# attiny_pwm.net
KiCad netlist of a schematic drawn in EAGLE
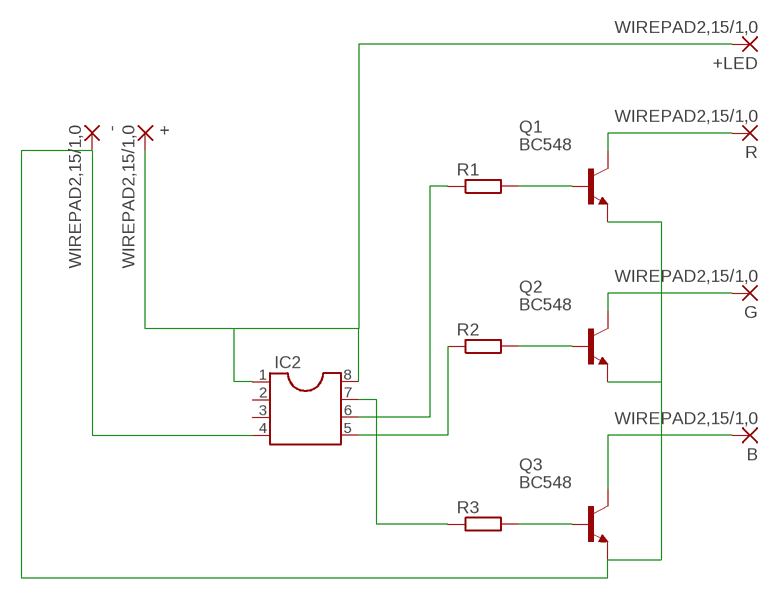
[diagram p0: schematic, sheet 1]

(export (version "E")
  (design (tool "Eeschema 10.0.6"))
  (components
    (comp (ref "+")
      (value "WIREPAD2,15/1,0")
      (footprint "eagle-import:2,15_1,0")
      (libsource (lib "eagle-import") (part "WIREPAD2,15/1,0"))
    )
    (comp (ref "+LED")
      (value "WIREPAD2,15/1,0")
      (footprint "eagle-import:2,15_1,0")
      (libsource (lib "eagle-import") (part "WIREPAD2,15/1,0"))
    )
    (comp (ref "-")
      (value "WIREPAD2,15/1,0")
      (footprint "eagle-import:2,15_1,0")
      (libsource (lib "eagle-import") (part "WIREPAD2,15/1,0"))
    )
    (comp (ref "B")
      (value "WIREPAD2,15/1,0")
      (footprint "eagle-import:2,15_1,0")
      (libsource (lib "eagle-import") (part "WIREPAD2,15/1,0"))
    )
    (comp (ref "G")
      (value "WIREPAD2,15/1,0")
      (footprint "eagle-import:2,15_1,0")
      (libsource (lib "eagle-import") (part "WIREPAD2,15/1,0"))
    )
    (comp (ref "IC2")
      (value "DIL8")
      (footprint "eagle-import:DIL08")
      (libsource (lib "eagle-import") (part "DIL8"))
    )
    (comp (ref "Q1")
      (value "BC548")
      (footprint "eagle-import:TO92-EBC")
      (libsource (lib "eagle-import") (part "BC548"))
    )
    (comp (ref "Q2")
      (value "BC548")
      (footprint "eagle-import:TO92-EBC")
      (libsource (lib "eagle-import") (part "BC548"))
    )
    (comp (ref "Q3")
      (value "BC548")
      (footprint "eagle-import:TO92-EBC")
      (libsource (lib "eagle-import") (part "BC548"))
    )
    (comp (ref "R")
      (value "WIREPAD2,15/1,0")
      (footprint "eagle-import:2,15_1,0")
      (libsource (lib "eagle-import") (part "WIREPAD2,15/1,0"))
    )
    (comp (ref "R1")
      (value "R-EU_0207/10")
      (footprint "eagle-import:0207_10")
      (libsource (lib "eagle-import") (part "R-EU_0207/10"))
    )
    (comp (ref "R2")
      (value "R-EU_0207/10")
      (footprint "eagle-import:0207_10")
      (libsource (lib "eagle-import") (part "R-EU_0207/10"))
    )
    (comp (ref "R3")
      (value "R-EU_0207/10")
      (footprint "eagle-import:0207_10")
      (libsource (lib "eagle-import") (part "R-EU_0207/10"))
    )
  )
  (nets
    (net (code "1") (name "Net-(+-P)") (class "Default")
      (node (ref "+") (pin "1") (pinfunction "P_1") (pintype "passive"))
      (node (ref "+LED") (pin "1") (pinfunction "P_1") (pintype "passive"))
      (node (ref "IC2") (pin "1") (pinfunction "1_1") (pintype "passive"))
      (node (ref "IC2") (pin "8") (pinfunction "8_8") (pintype "passive"))
    )
    (net (code "2") (name "Net-(--P)") (class "Default")
      (node (ref "-") (pin "1") (pinfunction "P_1") (pintype "passive"))
      (node (ref "IC2") (pin "4") (pinfunction "4_4") (pintype "passive"))
      (node (ref "Q1") (pin "E") (pinfunction "E_E") (pintype "passive"))
      (node (ref "Q2") (pin "E") (pinfunction "E_E") (pintype "passive"))
      (node (ref "Q3") (pin "E") (pinfunction "E_E") (pintype "passive"))
    )
    (net (code "3") (name "Net-(B-P)") (class "Default")
      (node (ref "B") (pin "1") (pinfunction "P_1") (pintype "passive"))
      (node (ref "Q3") (pin "C") (pinfunction "C_C") (pintype "passive"))
    )
    (net (code "4") (name "Net-(G-P)") (class "Default")
      (node (ref "G") (pin "1") (pinfunction "P_1") (pintype "passive"))
      (node (ref "Q2") (pin "C") (pinfunction "C_C") (pintype "passive"))
    )
    (net (code "5") (name "Net-(IC2-Pad5)") (class "Default")
      (node (ref "IC2") (pin "5") (pinfunction "5_5") (pintype "passive"))
      (node (ref "R2") (pin "1") (pinfunction "1_1") (pintype "passive"))
    )
    (net (code "6") (name "Net-(IC2-Pad6)") (class "Default")
      (node (ref "IC2") (pin "6") (pinfunction "6_6") (pintype "passive"))
      (node (ref "R1") (pin "1") (pinfunction "1_1") (pintype "passive"))
    )
    (net (code "7") (name "Net-(IC2-Pad7)") (class "Default")
      (node (ref "IC2") (pin "7") (pinfunction "7_7") (pintype "passive"))
      (node (ref "R3") (pin "1") (pinfunction "1_1") (pintype "passive"))
    )
    (net (code "8") (name "Net-(Q1-PadB)") (class "Default")
      (node (ref "Q1") (pin "B") (pinfunction "B_B") (pintype "passive"))
      (node (ref "R1") (pin "2") (pinfunction "2_2") (pintype "passive"))
    )
    (net (code "9") (name "Net-(Q2-PadB)") (class "Default")
      (node (ref "Q2") (pin "B") (pinfunction "B_B") (pintype "passive"))
      (node (ref "R2") (pin "2") (pinfunction "2_2") (pintype "passive"))
    )
    (net (code "10") (name "Net-(Q3-PadB)") (class "Default")
      (node (ref "Q3") (pin "B") (pinfunction "B_B") (pintype "passive"))
      (node (ref "R3") (pin "2") (pinfunction "2_2") (pintype "passive"))
    )
    (net (code "11") (name "Net-(R-P)") (class "Default")
      (node (ref "Q1") (pin "C") (pinfunction "C_C") (pintype "passive"))
      (node (ref "R") (pin "1") (pinfunction "P_1") (pintype "passive"))
    )
    (net (code "12") (name "unconnected-(IC2-Pad2)") (class "Default")
      (node (ref "IC2") (pin "2") (pinfunction "2_2") (pintype "passive"))
    )
    (net (code "13") (name "unconnected-(IC2-Pad3)") (class "Default")
      (node (ref "IC2") (pin "3") (pinfunction "3_3") (pintype "passive"))
    )
  )
)
